# Single_cell_module.net
KiCad netlist of a schematic drawn in Altium Designer
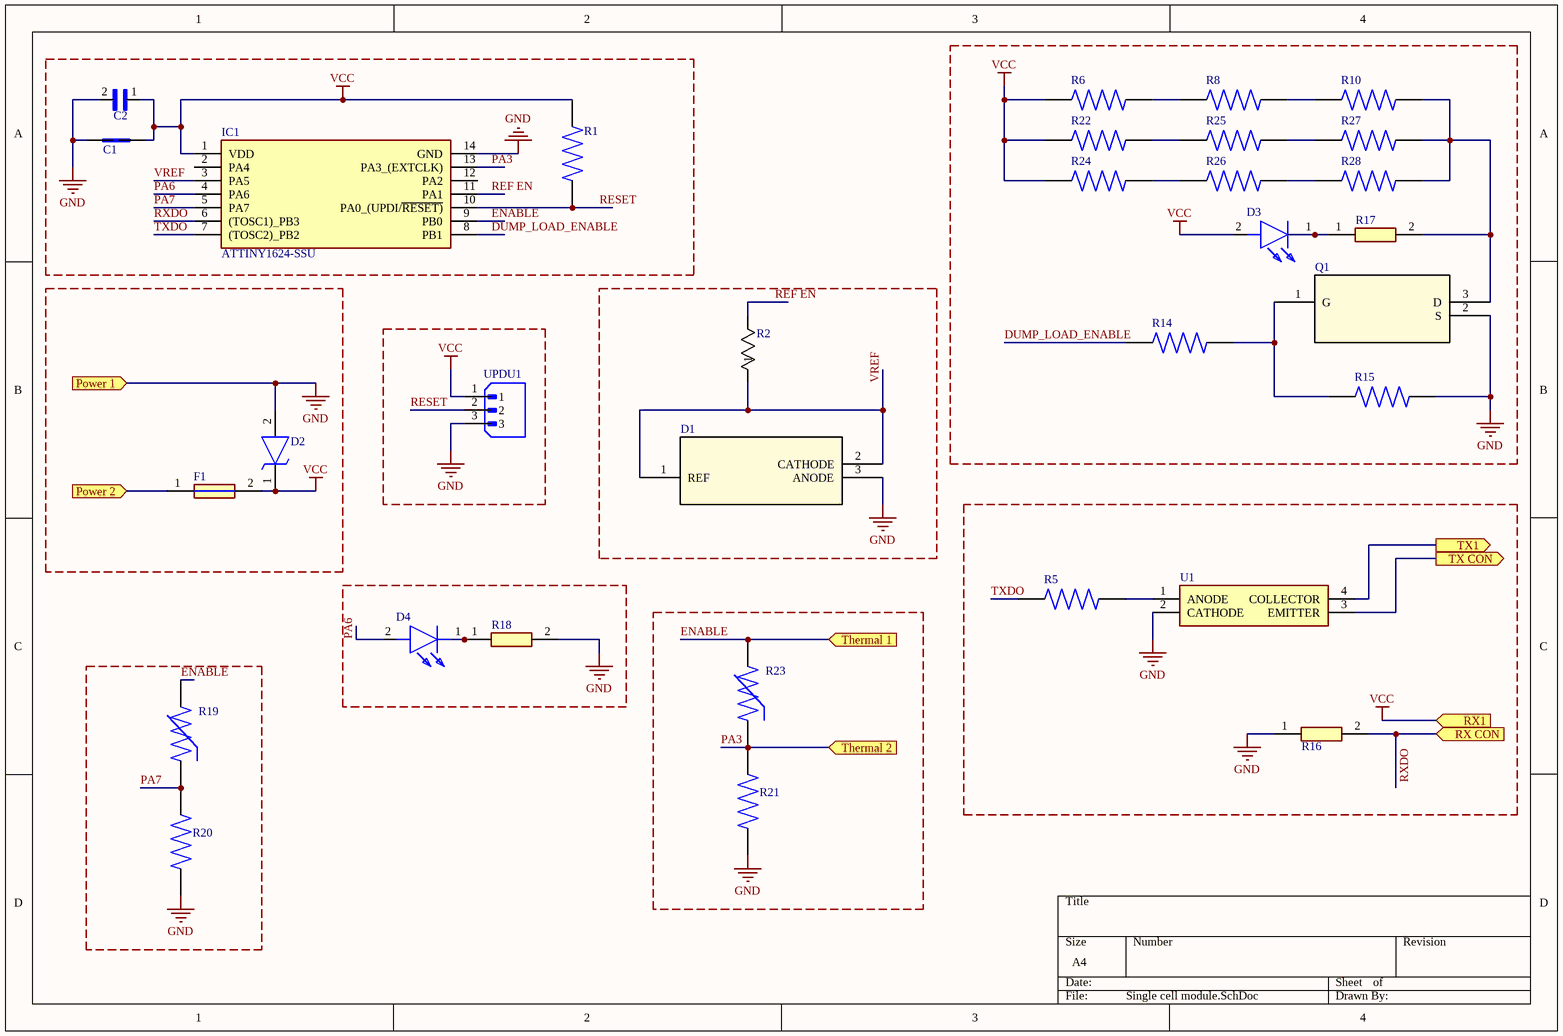
[diagram p0: Single cell module.SchDoc]

(export (version "E")
  (design (tool "Eeschema 10.0.6"))
  (components
    (comp (ref "C1")
      (value "CC0805KRX7R9BB104")
      (footprint "CAPC2012X70")
      (description "0.1ÂµF Â±10% 50V Ceramic Capacitor X7R 0805 _2012 Metric_")
      (fields (field (name "MF") "Yageo"))
      (libsource (lib "CC0805KRX7R9BB104") (part "CC0805KRX7R9BB104"))
    )
    (comp (ref "C2")
      (value "CL21A106KAYNNNE")
      (footprint "CAPC2012X135N")
      (description "10ÂµF Â±10% 25V Ceramic Capacitor X5R 0805 (2012 Metric)")
      (fields (field (name "MF") "Samsung") (field (name "DIGI-KEY_PART_NUMBER") "1276-2891-1-ND"))
      (libsource (lib "CL21A106KAYNNNE") (part "CL21A106KAYNNNE"))
    )
    (comp (ref "D1")
      (value "AZ432ANTR-E1")
      (footprint "SOT-23_DIO")
      (description "No Description Available")
      (libsource (lib "AZ432ANTR-E1") (part "AZ432ANTR-E1"))
    )
    (comp (ref "D2")
      (value "SM6T6V8A")
      (footprint "SamacSys:DIOM5436X265N")
      (description "TVS Diode (Uni-directional)")
      (fields (field (name "MOUSER PART NUMBER") "511-SM6T6V8A"))
      (libsource (lib "*") (part "SM6T6V8A"))
    )
    (comp (ref "D3")
      (value "19-217_GHC-YR1S2_3T")
      (footprint "SamacSys:LEDC1608X50N")
      (description "LED")
      (fields
        (field (name "MANUFACTURER_PART_NUMBER") "19-217/GHC-YR1S2/3T")
        (field (name "MOUSER PART NUMBER") "638-19217GHCYR1S23T")
      )
      (libsource (lib "*") (part "19-217_GHC-YR1S2_3T"))
    )
    (comp (ref "D4")
      (value "19-217_GHC-YR1S2_3T")
      (footprint "SamacSys:LEDC1608X50N")
      (description "LED")
      (fields
        (field (name "MANUFACTURER_PART_NUMBER") "19-217/GHC-YR1S2/3T")
        (field (name "MOUSER PART NUMBER") "638-19217GHCYR1S23T")
      )
      (libsource (lib "*") (part "19-217_GHC-YR1S2_3T"))
    )
    (comp (ref "F1")
      (value "MF-MSMF150-2")
      (footprint "SamacSys:FUSC4632X85N")
      (description "Fuse")
      (fields (field (name "MOUSER PART NUMBER") "652-MF-MSMF150-2"))
      (libsource (lib "*") (part "MF-MSMF150-2"))
    )
    (comp (ref "IC1")
      (value "ATTINY1624-SSU")
      (footprint "SamacSys:SOIC127P600X175-14N")
      (description "Integrated Circuit")
      (fields (field (name "MOUSER PART NUMBER") "556-ATTINY1624-SSU"))
      (libsource (lib "*") (part "ATTINY1624-SSU"))
    )
    (comp (ref "Q1")
      (value "AO3400A")
      (footprint "SOT-23-3L_AOS")
      (description "No Description Available")
      (libsource (lib "AO3400A") (part "AO3400A"))
    )
    (comp (ref "R1")
      (value "ERA6ARW104V")
      (footprint "RES_ERA6ARW104V")
      (libsource (lib "ERA6ARW104V") (part "ERA6ARW104V"))
    )
    (comp (ref "R2")
      (value "0805W8F1001T5E")
      (footprint "RES_8F1001T5E_UNR")
      (description "No Description Available")
      (libsource (lib "0805W8F1001T5E") (part "0805W8F1001T5E"))
    )
    (comp (ref "R5")
      (value "ERJ6ENF1800V")
      (footprint "RES_ERJ6ENF1800V")
      (libsource (lib "ERJ6ENF1800V") (part "ERJ6ENF1800V"))
    )
    (comp (ref "R6")
      (value "ERA6ARW104V")
      (footprint "RES_ERA6ARW104V")
      (libsource (lib "ERA6ARW104V") (part "ERA6ARW104V"))
    )
    (comp (ref "R8")
      (value "ERA6ARW104V")
      (footprint "RES_ERA6ARW104V")
      (libsource (lib "ERA6ARW104V") (part "ERA6ARW104V"))
    )
    (comp (ref "R10")
      (value "ERA6ARW104V")
      (footprint "RES_ERA6ARW104V")
      (libsource (lib "ERA6ARW104V") (part "ERA6ARW104V"))
    )
    (comp (ref "R14")
      (value "RT1206DRD07510RL")
      (footprint "RESC3116X65N")
      (description "RES SMD 510 OHM 0.5% 1/8W 1206")
      (libsource (lib "RT1206DRD07510RL") (part "RT1206DRD07510RL"))
    )
    (comp (ref "R15")
      (value "ERJP06D1002V")
      (footprint "RES_ERJP06D1002V")
      (libsource (lib "ERJP06D1002V") (part "ERJP06D1002V"))
    )
    (comp (ref "R16")
      (value "0805W8F2201T5E")
      (footprint "SamacSys:RESC2013X65N")
      (description "Resistor")
      (fields (field (name "MOUSER PART NUMBER") "303-0805W8F2201T5E"))
      (libsource (lib "*") (part "0805W8F2201T5E"))
    )
    (comp (ref "R17")
      (value "0805W8F2201T5E")
      (footprint "SamacSys:RESC2013X65N")
      (description "Resistor")
      (fields (field (name "MOUSER PART NUMBER") "303-0805W8F2201T5E"))
      (libsource (lib "*") (part "0805W8F2201T5E"))
    )
    (comp (ref "R18")
      (value "0805W8F2201T5E")
      (footprint "SamacSys:RESC2013X65N")
      (description "Resistor")
      (fields (field (name "MOUSER PART NUMBER") "303-0805W8F2201T5E"))
      (libsource (lib "*") (part "0805W8F2201T5E"))
    )
    (comp (ref "R19")
      (value "NCP18WF104J03RB")
      (footprint "THRMC1608X95N")
      (description "NTC Thermistor 100k 0603 (1608 Metric)")
      (fields (field (name "MF") "Murata Electronics"))
      (libsource (lib "NCP18WF104J03RB") (part "NCP18WF104J03RB"))
    )
    (comp (ref "R20")
      (value "ERJP06D1002V")
      (footprint "RES_ERJP06D1002V")
      (libsource (lib "ERJP06D1002V") (part "ERJP06D1002V"))
    )
    (comp (ref "R21")
      (value "ERJP06D1002V")
      (footprint "RES_ERJP06D1002V")
      (libsource (lib "ERJP06D1002V") (part "ERJP06D1002V"))
    )
    (comp (ref "R22")
      (value "ERA6ARW104V")
      (footprint "RES_ERA6ARW104V")
      (libsource (lib "ERA6ARW104V") (part "ERA6ARW104V"))
    )
    (comp (ref "R23")
      (value "NCP18WF104J03RB")
      (footprint "THRMC1608X95N")
      (description "NTC Thermistor 100k 0603 (1608 Metric)")
      (fields (field (name "MF") "Murata Electronics"))
      (libsource (lib "NCP18WF104J03RB") (part "NCP18WF104J03RB"))
    )
    (comp (ref "R24")
      (value "ERA6ARW104V")
      (footprint "RES_ERA6ARW104V")
      (libsource (lib "ERA6ARW104V") (part "ERA6ARW104V"))
    )
    (comp (ref "R25")
      (value "ERA6ARW104V")
      (footprint "RES_ERA6ARW104V")
      (libsource (lib "ERA6ARW104V") (part "ERA6ARW104V"))
    )
    (comp (ref "R26")
      (value "ERA6ARW104V")
      (footprint "RES_ERA6ARW104V")
      (libsource (lib "ERA6ARW104V") (part "ERA6ARW104V"))
    )
    (comp (ref "R27")
      (value "ERA6ARW104V")
      (footprint "RES_ERA6ARW104V")
      (libsource (lib "ERA6ARW104V") (part "ERA6ARW104V"))
    )
    (comp (ref "R28")
      (value "ERA6ARW104V")
      (footprint "RES_ERA6ARW104V")
      (libsource (lib "ERA6ARW104V") (part "ERA6ARW104V"))
    )
    (comp (ref "U1")
      (value "EL3H7_B__TA_-G")
      (footprint "SamacSys:SOIC127P700X200-4N")
      (description "Integrated Circuit")
      (fields
        (field (name "MANUFACTURER_PART_NUMBER") "EL3H7(B)(TA)-G")
        (field (name "MOUSER PART NUMBER") "638-EL3H7BTAG")
      )
      (libsource (lib "*") (part "EL3H7_B__TA_-G"))
    )
    (comp (ref "UPDU1")
      (value "B3B-XH-A_(LF)(SN)")
      (footprint "JST_B3B-XH-A (LF)(SN)")
      (description "Connector Header Through Hole 3 position 0.098 (2.50mm)")
      (fields (field (name "MF") "JST Sales America Inc.") (field (name "MP") "B3B-XH-A (LF)(SN)"))
      (libsource (lib "B3B-XH-A__LF__SN_") (part "B3B-XH-A_(LF)(SN)"))
    )
  )
  (nets
    (net (code "1") (name "/DUMP_LOAD_ENABLE") (class "Default")
      (node (ref "IC1") (pin "8") (pinfunction "PB1_8") (pintype "passive"))
      (node (ref "R14") (pin "1") (pinfunction "1_1") (pintype "passive"))
    )
    (net (code "2") (name "/ENABLE") (class "Default")
      (node (ref "IC1") (pin "9") (pinfunction "PB0_9") (pintype "passive"))
      (node (ref "R19") (pin "2") (pinfunction "2_2") (pintype "passive"))
      (node (ref "R23") (pin "2") (pinfunction "2_2") (pintype "passive"))
    )
    (net (code "3") (name "/PA3") (class "Default")
      (node (ref "IC1") (pin "13") (pinfunction "PA3_(EXTCLK)_13") (pintype "passive"))
      (node (ref "R21") (pin "2") (pinfunction "2_2") (pintype "passive"))
      (node (ref "R23") (pin "1") (pinfunction "1_1") (pintype "passive"))
    )
    (net (code "4") (name "/PA6") (class "Default")
      (node (ref "D4") (pin "2") (pinfunction "A_2") (pintype "passive"))
      (node (ref "IC1") (pin "4") (pinfunction "PA6_4") (pintype "passive"))
    )
    (net (code "5") (name "/PA7") (class "Default")
      (node (ref "IC1") (pin "5") (pinfunction "PA7_5") (pintype "passive"))
      (node (ref "R19") (pin "1") (pinfunction "1_1") (pintype "passive"))
      (node (ref "R20") (pin "2") (pinfunction "2_2") (pintype "passive"))
    )
    (net (code "6") (name "/Power 2") (class "Default")
      (node (ref "F1") (pin "1") (pinfunction "1_1") (pintype "passive"))
    )
    (net (code "7") (name "/REF EN") (class "Default")
      (node (ref "IC1") (pin "11") (pinfunction "PA1_11") (pintype "passive"))
      (node (ref "R2") (pin "2") (pinfunction "2_2") (pintype "passive"))
    )
    (net (code "8") (name "/RESET") (class "Default")
      (node (ref "IC1") (pin "10") (pinfunction "PA0_(UPDI/~{RESET)}_10") (pintype "passive"))
      (node (ref "R1") (pin "1") (pinfunction "1_1") (pintype "passive"))
      (node (ref "UPDU1") (pin "2") (pinfunction "2_2") (pintype "passive"))
    )
    (net (code "9") (name "/RXDO") (class "Default")
      (node (ref "IC1") (pin "6") (pinfunction "(TOSC1)_PB3_6") (pintype "passive"))
      (node (ref "R16") (pin "2") (pinfunction "2_2") (pintype "passive"))
    )
    (net (code "10") (name "/TX CON") (class "Default")
      (node (ref "U1") (pin "3") (pinfunction "EMITTER_3") (pintype "passive"))
    )
    (net (code "11") (name "/TX1") (class "Default")
      (node (ref "U1") (pin "4") (pinfunction "COLLECTOR_4") (pintype "passive"))
    )
    (net (code "12") (name "/TXDO") (class "Default")
      (node (ref "IC1") (pin "7") (pinfunction "(TOSC2)_PB2_7") (pintype "passive"))
      (node (ref "R5") (pin "1") (pinfunction "1_1") (pintype "passive"))
    )
    (net (code "13") (name "/VREF") (class "Default")
      (node (ref "D1") (pin "1") (pinfunction "REF_1") (pintype "passive"))
      (node (ref "D1") (pin "2") (pinfunction "CATHODE_2") (pintype "passive"))
      (node (ref "IC1") (pin "3") (pinfunction "PA5_3") (pintype "passive"))
      (node (ref "R2") (pin "1") (pinfunction "1_1") (pintype "passive"))
    )
    (net (code "14") (name "GND") (class "Default")
      (node (ref "C1") (pin "1") (pinfunction "1_1") (pintype "passive"))
      (node (ref "C2") (pin "2") (pinfunction "2_2") (pintype "passive"))
      (node (ref "D1") (pin "3") (pinfunction "ANODE_3") (pintype "passive"))
      (node (ref "D2") (pin "2") (pinfunction "A_2") (pintype "passive"))
      (node (ref "IC1") (pin "14") (pinfunction "GND_14") (pintype "passive"))
      (node (ref "Q1") (pin "2") (pinfunction "S_2") (pintype "passive"))
      (node (ref "R15") (pin "2") (pinfunction "2_2") (pintype "passive"))
      (node (ref "R16") (pin "1") (pinfunction "1_1") (pintype "passive"))
      (node (ref "R18") (pin "2") (pinfunction "2_2") (pintype "passive"))
      (node (ref "R20") (pin "1") (pinfunction "1_1") (pintype "passive"))
      (node (ref "R21") (pin "1") (pinfunction "1_1") (pintype "passive"))
      (node (ref "U1") (pin "2") (pinfunction "CATHODE_2") (pintype "passive"))
      (node (ref "UPDU1") (pin "3") (pinfunction "3_3") (pintype "passive"))
    )
    (net (code "15") (name "Net-(D3-K)") (class "Default")
      (node (ref "D3") (pin "1") (pinfunction "K_1") (pintype "passive"))
      (node (ref "R17") (pin "1") (pinfunction "1_1") (pintype "passive"))
    )
    (net (code "16") (name "Net-(D4-K)") (class "Default")
      (node (ref "D4") (pin "1") (pinfunction "K_1") (pintype "passive"))
      (node (ref "R18") (pin "1") (pinfunction "1_1") (pintype "passive"))
    )
    (net (code "17") (name "Net-(Q1-D)") (class "Default")
      (node (ref "Q1") (pin "3") (pinfunction "D_3") (pintype "passive"))
      (node (ref "R10") (pin "2") (pinfunction "2_2") (pintype "passive"))
      (node (ref "R17") (pin "2") (pinfunction "2_2") (pintype "passive"))
      (node (ref "R27") (pin "2") (pinfunction "2_2") (pintype "passive"))
      (node (ref "R28") (pin "2") (pinfunction "2_2") (pintype "passive"))
    )
    (net (code "18") (name "Net-(Q1-G)") (class "Default")
      (node (ref "Q1") (pin "1") (pinfunction "G_1") (pintype "passive"))
      (node (ref "R14") (pin "2") (pinfunction "2_2") (pintype "passive"))
      (node (ref "R15") (pin "1") (pinfunction "1_1") (pintype "passive"))
    )
    (net (code "19") (name "Net-(R6-Pad2)") (class "Default")
      (node (ref "R6") (pin "2") (pinfunction "2_2") (pintype "passive"))
      (node (ref "R8") (pin "1") (pinfunction "1_1") (pintype "passive"))
    )
    (net (code "20") (name "Net-(R10-Pad1)") (class "Default")
      (node (ref "R10") (pin "1") (pinfunction "1_1") (pintype "passive"))
      (node (ref "R8") (pin "2") (pinfunction "2_2") (pintype "passive"))
    )
    (net (code "21") (name "Net-(R22-Pad2)") (class "Default")
      (node (ref "R22") (pin "2") (pinfunction "2_2") (pintype "passive"))
      (node (ref "R25") (pin "1") (pinfunction "1_1") (pintype "passive"))
    )
    (net (code "22") (name "Net-(R24-Pad2)") (class "Default")
      (node (ref "R24") (pin "2") (pinfunction "2_2") (pintype "passive"))
      (node (ref "R26") (pin "1") (pinfunction "1_1") (pintype "passive"))
    )
    (net (code "23") (name "Net-(R25-Pad2)") (class "Default")
      (node (ref "R25") (pin "2") (pinfunction "2_2") (pintype "passive"))
      (node (ref "R27") (pin "1") (pinfunction "1_1") (pintype "passive"))
    )
    (net (code "24") (name "Net-(R26-Pad2)") (class "Default")
      (node (ref "R26") (pin "2") (pinfunction "2_2") (pintype "passive"))
      (node (ref "R28") (pin "1") (pinfunction "1_1") (pintype "passive"))
    )
    (net (code "25") (name "Net-(U1-ANODE)") (class "Default")
      (node (ref "R5") (pin "2") (pinfunction "2_2") (pintype "passive"))
      (node (ref "U1") (pin "1") (pinfunction "ANODE_1") (pintype "passive"))
    )
    (net (code "26") (name "VCC") (class "Default")
      (node (ref "C1") (pin "2") (pinfunction "2_2") (pintype "passive"))
      (node (ref "C2") (pin "1") (pinfunction "1_1") (pintype "passive"))
      (node (ref "D2") (pin "1") (pinfunction "K_1") (pintype "passive"))
      (node (ref "D3") (pin "2") (pinfunction "A_2") (pintype "passive"))
      (node (ref "F1") (pin "2") (pinfunction "2_2") (pintype "passive"))
      (node (ref "IC1") (pin "1") (pinfunction "VDD_1") (pintype "passive"))
      (node (ref "R1") (pin "2") (pinfunction "2_2") (pintype "passive"))
      (node (ref "R22") (pin "1") (pinfunction "1_1") (pintype "passive"))
      (node (ref "R24") (pin "1") (pinfunction "1_1") (pintype "passive"))
      (node (ref "R6") (pin "1") (pinfunction "1_1") (pintype "passive"))
      (node (ref "UPDU1") (pin "1") (pinfunction "1_1") (pintype "passive"))
    )
    (net (code "27") (name "unconnected-(IC1-PA2-Pad12)") (class "Default")
      (node (ref "IC1") (pin "12") (pinfunction "PA2_12") (pintype "passive"))
    )
    (net (code "28") (name "unconnected-(IC1-PA4-Pad2)") (class "Default")
      (node (ref "IC1") (pin "2") (pinfunction "PA4_2") (pintype "passive"))
    )
  )
)
